# d1-mini.net
KiCad netlist of a schematic drawn in EAGLE
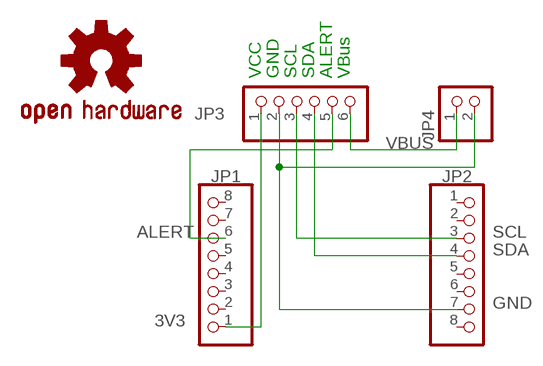
[diagram p0: schematic, sheet 1]

(export (version "E")
  (design (tool "Eeschema 10.0.6"))
  (components
    (comp (ref "JP1")
      (value "PINHD-1X8")
      (footprint "eagle-import:1X08")
      (libsource (lib "eagle-import") (part "PINHD-1X8"))
    )
    (comp (ref "JP2")
      (value "PINHD-1X8")
      (footprint "eagle-import:1X08")
      (libsource (lib "eagle-import") (part "PINHD-1X8"))
    )
    (comp (ref "JP3")
      (value "PINHD-1X6")
      (footprint "eagle-import:1X06")
      (libsource (lib "eagle-import") (part "PINHD-1X6"))
    )
    (comp (ref "JP4")
      (value "PINHD-1X2/90")
      (footprint "eagle-import:1X02_90")
      (libsource (lib "eagle-import") (part "PINHD-1X2/90"))
    )
    (comp (ref "LOGO1")
      (value "OSHW-LOGOS")
      (footprint "eagle-import:OSHW-LOGO-S")
      (libsource (lib "eagle-import") (part "OSHW-LOGOS"))
    )
  )
  (nets
    (net (code "1") (name "/3V3") (class "Default")
      (node (ref "JP1") (pin "1") (pinfunction "1_1") (pintype "passive"))
      (node (ref "JP3") (pin "1") (pinfunction "1_1") (pintype "passive"))
    )
    (net (code "2") (name "/ALERT") (class "Default")
      (node (ref "JP1") (pin "6") (pinfunction "6_6") (pintype "passive"))
      (node (ref "JP3") (pin "5") (pinfunction "5_5") (pintype "passive"))
    )
    (net (code "3") (name "/GND") (class "Default")
      (node (ref "JP2") (pin "7") (pinfunction "7_7") (pintype "passive"))
      (node (ref "JP3") (pin "2") (pinfunction "2_2") (pintype "passive"))
      (node (ref "JP4") (pin "2") (pinfunction "2_2") (pintype "passive"))
    )
    (net (code "4") (name "/SCL") (class "Default")
      (node (ref "JP2") (pin "3") (pinfunction "3_3") (pintype "passive"))
      (node (ref "JP3") (pin "3") (pinfunction "3_3") (pintype "passive"))
    )
    (net (code "5") (name "/SDA") (class "Default")
      (node (ref "JP2") (pin "4") (pinfunction "4_4") (pintype "passive"))
      (node (ref "JP3") (pin "4") (pinfunction "4_4") (pintype "passive"))
    )
    (net (code "6") (name "/VBUS") (class "Default")
      (node (ref "JP3") (pin "6") (pinfunction "6_6") (pintype "passive"))
      (node (ref "JP4") (pin "1") (pinfunction "1_1") (pintype "passive"))
    )
    (net (code "7") (name "unconnected-(JP1-Pad2)") (class "Default")
      (node (ref "JP1") (pin "2") (pinfunction "2_2") (pintype "passive"))
    )
    (net (code "8") (name "unconnected-(JP1-Pad3)") (class "Default")
      (node (ref "JP1") (pin "3") (pinfunction "3_3") (pintype "passive"))
    )
    (net (code "9") (name "unconnected-(JP1-Pad4)") (class "Default")
      (node (ref "JP1") (pin "4") (pinfunction "4_4") (pintype "passive"))
    )
    (net (code "10") (name "unconnected-(JP1-Pad5)") (class "Default")
      (node (ref "JP1") (pin "5") (pinfunction "5_5") (pintype "passive"))
    )
    (net (code "11") (name "unconnected-(JP1-Pad7)") (class "Default")
      (node (ref "JP1") (pin "7") (pinfunction "7_7") (pintype "passive"))
    )
    (net (code "12") (name "unconnected-(JP1-Pad8)") (class "Default")
      (node (ref "JP1") (pin "8") (pinfunction "8_8") (pintype "passive"))
    )
    (net (code "13") (name "unconnected-(JP2-Pad1)") (class "Default")
      (node (ref "JP2") (pin "1") (pinfunction "1_1") (pintype "passive"))
    )
    (net (code "14") (name "unconnected-(JP2-Pad2)") (class "Default")
      (node (ref "JP2") (pin "2") (pinfunction "2_2") (pintype "passive"))
    )
    (net (code "15") (name "unconnected-(JP2-Pad5)") (class "Default")
      (node (ref "JP2") (pin "5") (pinfunction "5_5") (pintype "passive"))
    )
    (net (code "16") (name "unconnected-(JP2-Pad6)") (class "Default")
      (node (ref "JP2") (pin "6") (pinfunction "6_6") (pintype "passive"))
    )
    (net (code "17") (name "unconnected-(JP2-Pad8)") (class "Default")
      (node (ref "JP2") (pin "8") (pinfunction "8_8") (pintype "passive"))
    )
  )
)
